# Arduino_sheet.net
KiCad netlist of a schematic drawn in Altium Designer
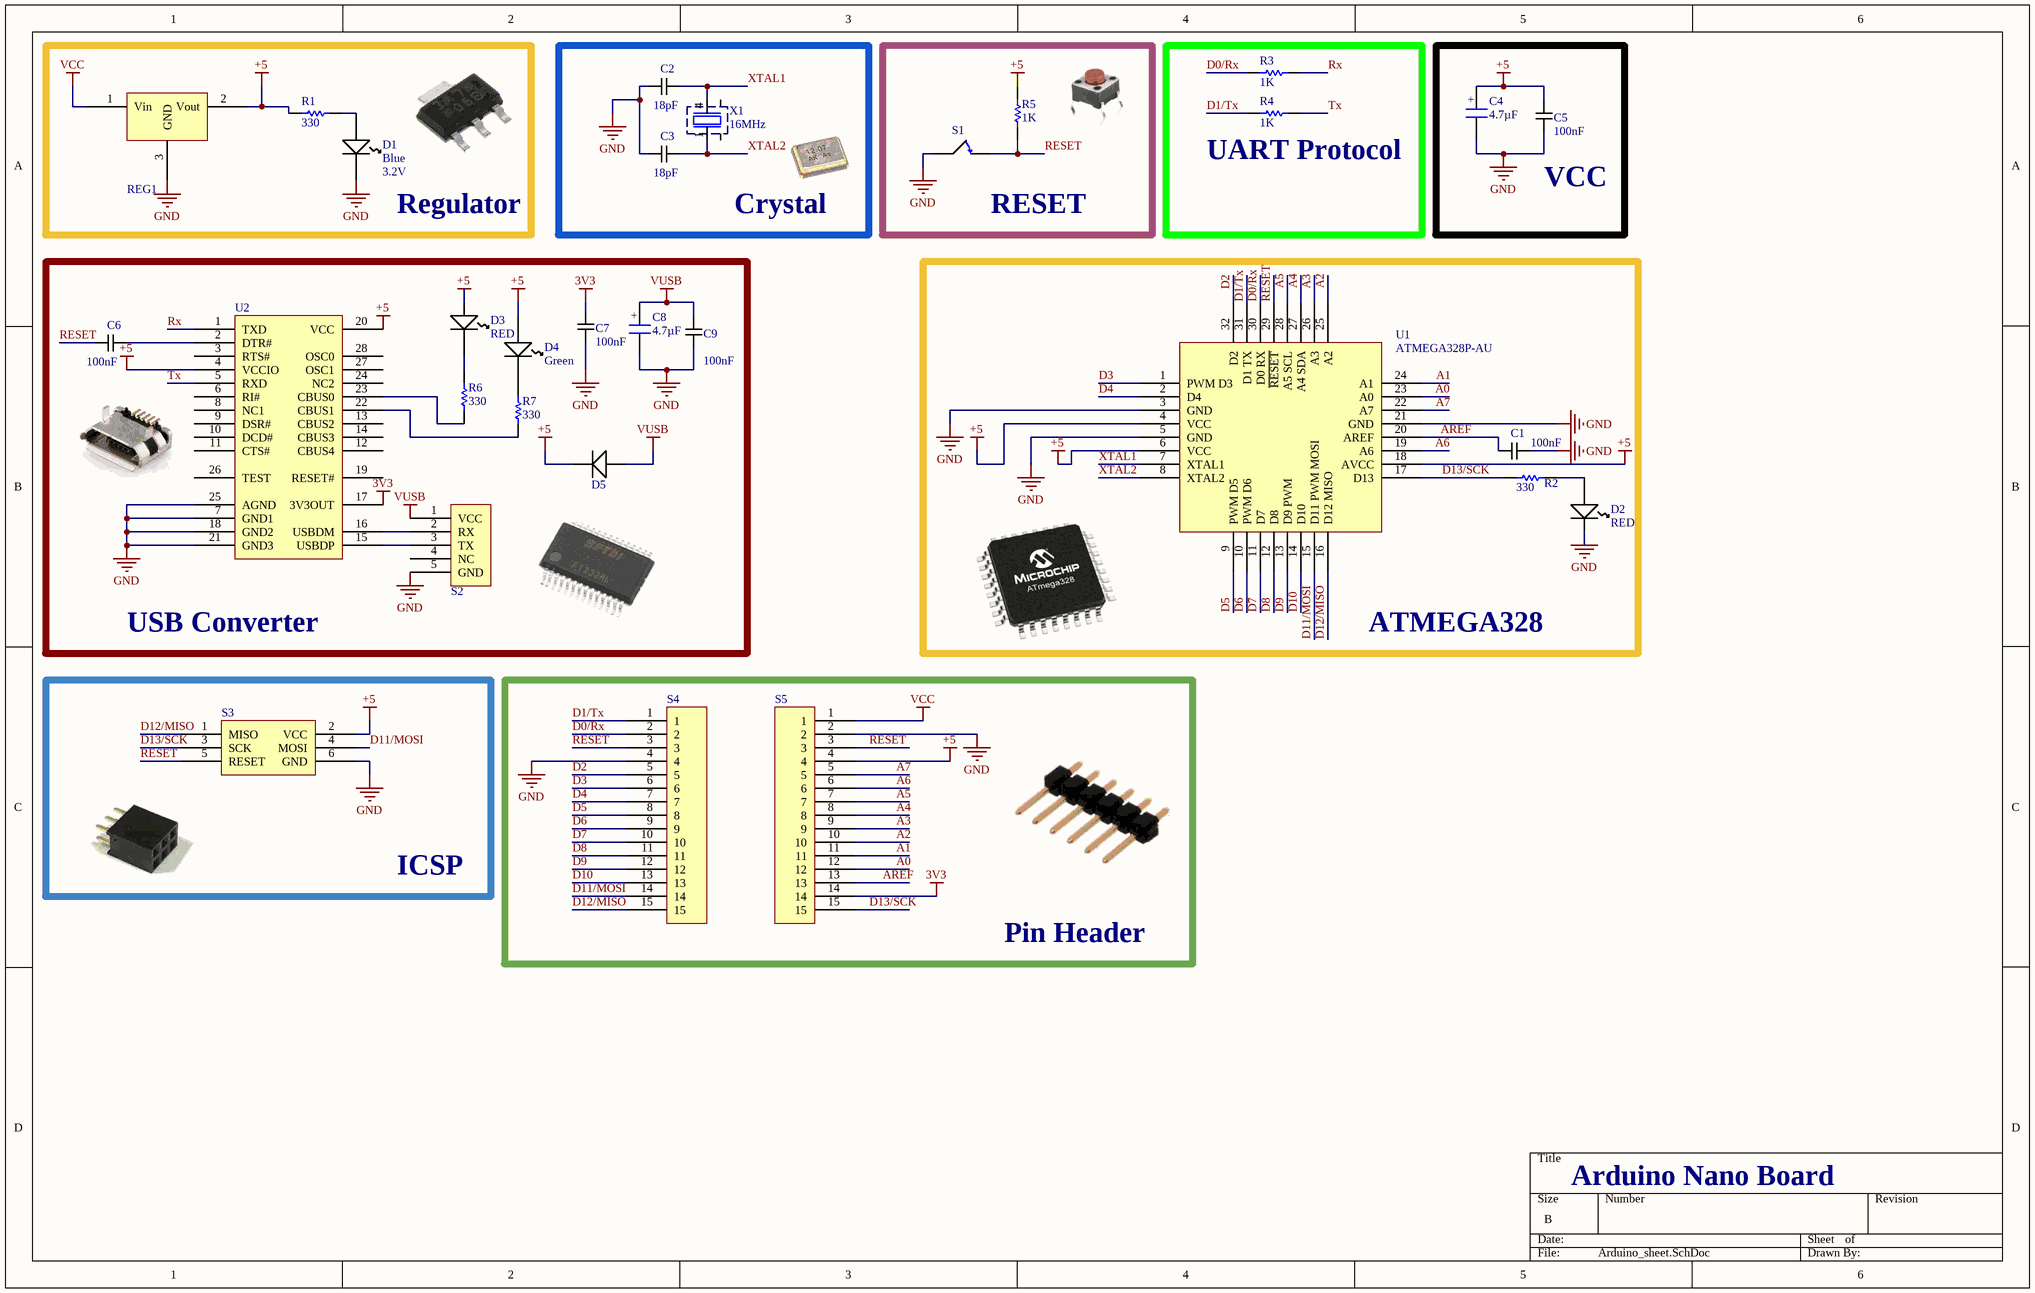
[diagram p0: Arduino_sheet.SchDoc]

(export (version "E")
  (design (tool "Eeschema 10.0.6"))
  (components
    (comp (ref "C1")
      (value "100nF Ceramic Multilayer Capacitor_1")
      (footprint "CAPCP2012X09N")
      (description "AVX 0805 Standard 100nF Ceramic Multilayer Capacitor, 50 V dc X7R Dielectric ±10% SMD")
      (fields
        (field (name "MANUFACTURER") "AVX")
        (field (name "VOLTAGE") "50V")
        (field (name "CAPACITANCE") "100nF")
        (field (name "CREATOR") "Ritesh Kanjee")
      )
      (libsource (lib "RS Components - Capacitors") (part "100nF Ceramic Multilayer Capacitor_1"))
    )
    (comp (ref "C2")
      (value "C0805C180J5GACTU")
      (footprint "CAPCP2012X09N")
      (description "18pF Ceramic Multilayer Capacitor, 50 V dc C0G Dielectric ±5% SMD")
      (fields
        (field (name "MANUFACTURER") "Kemet")
        (field (name "VOLTAGE") "50V")
        (field (name "CAPACITANCE") "18pF")
        (field (name "CREATOR") "Ritesh Kanjee")
      )
      (libsource (lib "RS Components - Capacitors") (part "18pF Ceramic Multilayer Capacitor, 50 V dc C0G Dielectric ±5% SMD"))
    )
    (comp (ref "C3")
      (value "C0805C180J5GACTU")
      (footprint "CAPCP2012X09N")
      (description "18pF Ceramic Multilayer Capacitor, 50 V dc C0G Dielectric ±5% SMD")
      (fields
        (field (name "MANUFACTURER") "Kemet")
        (field (name "VOLTAGE") "50V")
        (field (name "CAPACITANCE") "18pF")
        (field (name "CREATOR") "Ritesh Kanjee")
      )
      (libsource (lib "RS Components - Capacitors") (part "18pF Ceramic Multilayer Capacitor, 50 V dc C0G Dielectric ±5% SMD"))
    )
    (comp (ref "C4")
      (value "4.7µF")
      (footprint "CASE A - 3216X18")
      (description "Capacitor,tantalum,SMT,16V,4.7uF,10%,A-case")
      (fields
        (field (name "TOLERANCE") "10%")
        (field (name "VOLTAGE") "16V")
        (field (name "PUBLISHER") "DPSS")
      )
      (libsource (lib "RS Components - Capacitors") (part "4.7µF Tant RS 496-3545"))
    )
    (comp (ref "C5")
      (value "100nF Ceramic Multilayer Capacitor_1")
      (footprint "CAPCP2012X09N")
      (description "AVX 0805 Standard 100nF Ceramic Multilayer Capacitor, 50 V dc X7R Dielectric ±10% SMD")
      (fields
        (field (name "MANUFACTURER") "AVX")
        (field (name "VOLTAGE") "50V")
        (field (name "CAPACITANCE") "100nF")
        (field (name "CREATOR") "Ritesh Kanjee")
      )
      (libsource (lib "RS Components - Capacitors") (part "100nF Ceramic Multilayer Capacitor_1"))
    )
    (comp (ref "C6")
      (value "100nF Ceramic Multilayer Capacitor_1")
      (footprint "CAPCP2012X09N")
      (description "AVX 0805 Standard 100nF Ceramic Multilayer Capacitor, 50 V dc X7R Dielectric ±10% SMD")
      (fields
        (field (name "MANUFACTURER") "AVX")
        (field (name "VOLTAGE") "50V")
        (field (name "CAPACITANCE") "100nF")
        (field (name "CREATOR") "Ritesh Kanjee")
      )
      (libsource (lib "RS Components - Capacitors") (part "100nF Ceramic Multilayer Capacitor_1"))
    )
    (comp (ref "C7")
      (value "100nF Ceramic Multilayer Capacitor_1")
      (footprint "CAPCP2012X09N")
      (description "AVX 0805 Standard 100nF Ceramic Multilayer Capacitor, 50 V dc X7R Dielectric ±10% SMD")
      (fields
        (field (name "MANUFACTURER") "AVX")
        (field (name "VOLTAGE") "50V")
        (field (name "CAPACITANCE") "100nF")
        (field (name "CREATOR") "Ritesh Kanjee")
      )
      (libsource (lib "RS Components - Capacitors") (part "100nF Ceramic Multilayer Capacitor_1"))
    )
    (comp (ref "C8")
      (value "4.7µF")
      (footprint "CASE A - 3216X18")
      (description "Capacitor,tantalum,SMT,16V,4.7uF,10%,A-case")
      (fields
        (field (name "TOLERANCE") "10%")
        (field (name "VOLTAGE") "16V")
        (field (name "PUBLISHER") "DPSS")
      )
      (libsource (lib "RS Components - Capacitors") (part "4.7µF Tant RS 496-3545"))
    )
    (comp (ref "C9")
      (value "100nF Ceramic Multilayer Capacitor_1")
      (footprint "CAPCP2012X09N")
      (description "AVX 0805 Standard 100nF Ceramic Multilayer Capacitor, 50 V dc X7R Dielectric ±10% SMD")
      (fields
        (field (name "MANUFACTURER") "AVX")
        (field (name "VOLTAGE") "50V")
        (field (name "CAPACITANCE") "100nF")
        (field (name "CREATOR") "Ritesh Kanjee")
      )
      (libsource (lib "RS Components - Capacitors") (part "100nF Ceramic Multilayer Capacitor_1"))
    )
    (comp (ref "D1")
      (value "Kingbright Blue LED, 60 mcd 120 ° 0805")
      (footprint "LED1913X12NBLUE")
      (fields
        (field (name "MANUFACTURER") "KingBright")
        (field (name "MANUFACTURER PART NO.") "KP-2012PBC-A")
        (field (name "COLOR") "Blue")
        (field (name "FORWARD VOLTAGE") "3.2V")
        (field (name "CREATOR") "Ritesh Kanjee")
      )
      (libsource (lib "KingBright LEDs") (part "Kingbright Blue LED, 60 mcd 120 ° 0805"))
    )
    (comp (ref "D2")
      (value "Kingbright Red LED, 100 mcd 120 ° 0805")
      (footprint "LED1913X12NRED")
      (fields
        (field (name "MANUFACTURER") "KingBright")
        (field (name "MANUFACTURER PART NO.") "KP-2012SRC-PRV")
        (field (name "COLOR") "RED")
        (field (name "CREATOR") "Ritesh Kanjee")
      )
      (libsource (lib "KingBright LEDs") (part "Kingbright Red LED, 100 mcd 120 ° 0805"))
    )
    (comp (ref "D3")
      (value "Kingbright Red LED, 100 mcd 120 ° 0805")
      (footprint "LED1913X12NRED")
      (fields
        (field (name "MANUFACTURER") "KingBright")
        (field (name "MANUFACTURER PART NO.") "KP-2012SRC-PRV")
        (field (name "COLOR") "RED")
        (field (name "CREATOR") "Ritesh Kanjee")
      )
      (libsource (lib "KingBright LEDs") (part "Kingbright Red LED, 100 mcd 120 ° 0805"))
    )
    (comp (ref "D4")
      (value "Kingbright Green LED, 70 mcd 120 ° 0805")
      (footprint "LED1913X12NGREEN")
      (fields
        (field (name "MANUFACTURER") "KingBright")
        (field (name "MANUFACTURER PART NO.") "KP-2012MGC")
        (field (name "COLOR") "Green")
        (field (name "CREATOR") "Ritesh Kanjee")
      )
      (libsource (lib "KingBright LEDs") (part "Kingbright Green LED, 70 mcd 120 ° 0805"))
    )
    (comp (ref "D5")
      (value "Panasonic DB2J20900L Schottky Diode, 0.5A, 20V, 2.4ns, 2-Pin SMini2 F5 B")
      (footprint "DIOM1712X07N")
      (fields
        (field (name "MANUFACTURER") "Panasonic")
        (field (name "MANUFACTURER PART NO.") "DB2J20900L")
        (field (name "CREATED BY") "R Kanjee")
      )
      (libsource (lib "Panasonic Diodes") (part "Schottky Diode, 0.5A, 20V, 2.4ns, 2-Pin SMini2 F5 B"))
    )
    (comp (ref "R1")
      (value "330")
      (description "Resistor")
      (libsource (lib "Simulation Generic Components") (part "Resistor"))
    )
    (comp (ref "R2")
      (value "330")
      (description "Resistor")
      (libsource (lib "Simulation Generic Components") (part "Resistor"))
    )
    (comp (ref "R3")
      (value "1K")
      (description "Resistor")
      (libsource (lib "Simulation Generic Components") (part "Resistor"))
    )
    (comp (ref "R4")
      (value "1K")
      (description "Resistor")
      (libsource (lib "Simulation Generic Components") (part "Resistor"))
    )
    (comp (ref "R5")
      (value "1K")
      (description "Resistor")
      (libsource (lib "Simulation Generic Components") (part "Resistor"))
    )
    (comp (ref "R6")
      (value "330")
      (description "Resistor")
      (libsource (lib "Simulation Generic Components") (part "Resistor"))
    )
    (comp (ref "R7")
      (value "330")
      (description "Resistor")
      (libsource (lib "Simulation Generic Components") (part "Resistor"))
    )
    (comp (ref "REG1")
      (value "LM1117MP-5.0/NOPB, Low Dropout Voltage Regulator, 1.5A, 5 V ±1%, 4-Pin SOT-223")
      (footprint "SOT230P700X180-4N")
      (fields (field (name "MANUFACTURER") "Texas Instruments") (field (name "CREATED BY") "R Kanjee"))
      (libsource (lib "TI Low Dropout Voltage Regulator") (part "LM1117MP-5.0"))
    )
    (comp (ref "S1")
      (value "Tactile Switch SPST- NO 0.05A @24V")
      (footprint "Tactile Switch")
      (fields
        (field (name "MANUFACTURER") "Omron")
        (field (name "MANUFACTURER PART NO.") "B3F1000")
        (field (name "CREATOR") "R Kanjee")
      )
      (libsource (lib "Omron Tactile Switches") (part "Tactile Switch SPST- NO 0.05A @24V"))
    )
    (comp (ref "S2")
      (value "NewMolex Right Angle SMT Female Type B Micro USB Connector, 30 V ac, 1.8A")
      (footprint "MicroUSB")
      (fields
        (field (name "MANUFACTURER") "Molex")
        (field (name "MANUFACTURER PART NO.") "105017-0001")
        (field (name "CREATOR") "R Kanjee")
      )
      (libsource (lib "Molex Connectors") (part "Micro USB Connector, 30 V ac, 1.8A"))
    )
    (comp (ref "S3")
      (value "Programming Headers Dual Row")
      (footprint "ISP HEADER")
      (fields
        (field (name "MANUFACTURER") "FCI")
        (field (name "MANUFACTURER PART NO.") "68000-236HLF")
        (field (name "CREATED BY") "R Kanjee")
      )
      (libsource (lib "PCB Headers") (part "Programming ISP, Programming Headers Dual Row"))
    )
    (comp (ref "S4")
      (value "connector;str header;single row;.1 cont centers;.095 tail;gold or gtx;36 contact")
      (footprint "Header")
      (fields
        (field (name "MANUFACTURER") "FCI")
        (field (name "MANUFACTURER PART NO.") "68000-236HLF")
        (field (name "CREATED BY") "R Kanjee")
      )
      (libsource (lib "") (part "Single row; PCB headers_1"))
    )
    (comp (ref "S5")
      (value "connector;str header;single row;.1 cont centers;.095 tail;gold or gtx;36 contact")
      (footprint "Header")
      (fields
        (field (name "MANUFACTURER") "FCI")
        (field (name "MANUFACTURER PART NO.") "68000-236HLF")
        (field (name "CREATED BY") "R Kanjee")
      )
      (libsource (lib "PCB Headers") (part "Single row; PCB headers"))
    )
    (comp (ref "U1")
      (value "ATMEGA328P-AU")
      (footprint "TQFP80P900X900X120-32N")
      (description "ATMEGA328P-AU, 8 bit AVR Microcontroller 20MHz 1 kB, 32 kB Flash, 2 kB RAM, I2C 32-Pin TQFP")
      (fields (field (name "CREATED BY") "Ritesh Kanjee"))
      (libsource (lib "Atmel Microcontrollers") (part "ATMEGA328P-AU"))
    )
    (comp (ref "U2")
      (value "FT232RL, Universal Asynchronous Receiver & Transmitter 3MBd, 28-Pin, SSOP")
      (footprint "SOP65P780X200-28N")
      (fields
        (field (name "MANUFACTURER PART NO.") "FT232RL")
        (field (name "MANUFACTURER") "FTDI Chip")
        (field (name "CREATOR") "R Kanjee")
      )
      (libsource (lib "FTDI RS232toUSB") (part "FT232RL USB to UART, Universal Asynchronous Receiver & Transmitter 3MBd, 28-Pin, SSOP"))
    )
    (comp (ref "X1")
      (value "16MHz")
      (footprint "Aker S5C Crystal")
      (description "Aker S5C SMT Crystal")
      (fields
        (field (name "MANUFACTURER") "Aker")
        (field (name "MANUFACTURER PART #") "C5S-16.000-12-3030-X")
        (field (name "CREATOR") "R Kanjee")
      )
      (libsource (lib "Aker Crystals") (part "Aker  C5S-16.000-12-3030-X"))
    )
  )
  (nets
    (net (code "1") (name "+5") (class "Default")
      (node (ref "C4") (pin "1") (pinfunction "1_1") (pintype "passive"))
      (node (ref "C5") (pin "2") (pinfunction "2_2") (pintype "passive"))
      (node (ref "D3") (pin "1") (pinfunction "A_1") (pintype "passive"))
      (node (ref "D4") (pin "1") (pinfunction "A_1") (pintype "passive"))
      (node (ref "D5") (pin "1") (pinfunction "1_1") (pintype "passive"))
      (node (ref "R1") (pin "1") (pinfunction "1_1") (pintype "passive"))
      (node (ref "R5") (pin "2") (pinfunction "2_2") (pintype "passive"))
      (node (ref "REG1") (pin "2") (pinfunction "Vout_2") (pintype "passive"))
      (node (ref "S3") (pin "2") (pinfunction "VCC_2") (pintype "passive"))
      (node (ref "S5") (pin "4") (pinfunction "4_4") (pintype "passive"))
      (node (ref "U1") (pin "18") (pinfunction "AVCC_18") (pintype "passive"))
      (node (ref "U1") (pin "4") (pinfunction "VCC_4") (pintype "passive"))
      (node (ref "U1") (pin "6") (pinfunction "VCC_6") (pintype "passive"))
      (node (ref "U2") (pin "20") (pinfunction "VCC_20") (pintype "passive"))
      (node (ref "U2") (pin "4") (pinfunction "VCCIO_4") (pintype "passive"))
    )
    (net (code "2") (name "/A0") (class "Default")
      (node (ref "S5") (pin "12") (pinfunction "12_12") (pintype "passive"))
      (node (ref "U1") (pin "23") (pinfunction "A0_23") (pintype "passive"))
    )
    (net (code "3") (name "/A1") (class "Default")
      (node (ref "S5") (pin "11") (pinfunction "11_11") (pintype "passive"))
      (node (ref "U1") (pin "24") (pinfunction "A1_24") (pintype "passive"))
    )
    (net (code "4") (name "/A2") (class "Default")
      (node (ref "S5") (pin "10") (pinfunction "10_10") (pintype "passive"))
      (node (ref "U1") (pin "25") (pinfunction "A2_25") (pintype "passive"))
    )
    (net (code "5") (name "/A3") (class "Default")
      (node (ref "S5") (pin "9") (pinfunction "9_9") (pintype "passive"))
      (node (ref "U1") (pin "26") (pinfunction "A3_26") (pintype "passive"))
    )
    (net (code "6") (name "/A4") (class "Default")
      (node (ref "S5") (pin "8") (pinfunction "8_8") (pintype "passive"))
      (node (ref "U1") (pin "27") (pinfunction "A4_SDA_27") (pintype "passive"))
    )
    (net (code "7") (name "/A5") (class "Default")
      (node (ref "S5") (pin "7") (pinfunction "7_7") (pintype "passive"))
      (node (ref "U1") (pin "28") (pinfunction "A5_SCL_28") (pintype "passive"))
    )
    (net (code "8") (name "/A6") (class "Default")
      (node (ref "S5") (pin "6") (pinfunction "6_6") (pintype "passive"))
      (node (ref "U1") (pin "19") (pinfunction "A6_19") (pintype "passive"))
    )
    (net (code "9") (name "/A7") (class "Default")
      (node (ref "S5") (pin "5") (pinfunction "5_5") (pintype "passive"))
      (node (ref "U1") (pin "22") (pinfunction "A7_22") (pintype "passive"))
    )
    (net (code "10") (name "/AREF") (class "Default")
      (node (ref "C1") (pin "1") (pinfunction "1_1") (pintype "passive"))
      (node (ref "S5") (pin "13") (pinfunction "13_13") (pintype "passive"))
      (node (ref "U1") (pin "20") (pinfunction "AREF_20") (pintype "passive"))
    )
    (net (code "11") (name "/D0{slash}Rx") (class "Default")
      (node (ref "R3") (pin "1") (pinfunction "1_1") (pintype "passive"))
      (node (ref "S4") (pin "2") (pinfunction "2_2") (pintype "passive"))
      (node (ref "U1") (pin "30") (pinfunction "D0_RX_30") (pintype "passive"))
    )
    (net (code "12") (name "/D1{slash}Tx") (class "Default")
      (node (ref "R4") (pin "1") (pinfunction "1_1") (pintype "passive"))
      (node (ref "S4") (pin "1") (pinfunction "1_1") (pintype "passive"))
      (node (ref "U1") (pin "31") (pinfunction "D1_TX_31") (pintype "passive"))
    )
    (net (code "13") (name "/D2") (class "Default")
      (node (ref "S4") (pin "5") (pinfunction "5_5") (pintype "passive"))
      (node (ref "U1") (pin "32") (pinfunction "D2_32") (pintype "passive"))
    )
    (net (code "14") (name "/D3") (class "Default")
      (node (ref "S4") (pin "6") (pinfunction "6_6") (pintype "passive"))
      (node (ref "U1") (pin "1") (pinfunction "PWM_D3_1") (pintype "passive"))
    )
    (net (code "15") (name "/D4") (class "Default")
      (node (ref "S4") (pin "7") (pinfunction "7_7") (pintype "passive"))
      (node (ref "U1") (pin "2") (pinfunction "D4_2") (pintype "passive"))
    )
    (net (code "16") (name "/D5") (class "Default")
      (node (ref "S4") (pin "8") (pinfunction "8_8") (pintype "passive"))
      (node (ref "U1") (pin "9") (pinfunction "PWM_D5_9") (pintype "passive"))
    )
    (net (code "17") (name "/D6") (class "Default")
      (node (ref "S4") (pin "9") (pinfunction "9_9") (pintype "passive"))
      (node (ref "U1") (pin "10") (pinfunction "PWM_D6_10") (pintype "passive"))
    )
    (net (code "18") (name "/D7") (class "Default")
      (node (ref "S4") (pin "10") (pinfunction "10_10") (pintype "passive"))
      (node (ref "U1") (pin "11") (pinfunction "D7_11") (pintype "passive"))
    )
    (net (code "19") (name "/D8") (class "Default")
      (node (ref "S4") (pin "11") (pinfunction "11_11") (pintype "passive"))
      (node (ref "U1") (pin "12") (pinfunction "D8_12") (pintype "passive"))
    )
    (net (code "20") (name "/D9") (class "Default")
      (node (ref "S4") (pin "12") (pinfunction "12_12") (pintype "passive"))
      (node (ref "U1") (pin "13") (pinfunction "D9_PWM_13") (pintype "passive"))
    )
    (net (code "21") (name "/D10") (class "Default")
      (node (ref "S4") (pin "13") (pinfunction "13_13") (pintype "passive"))
      (node (ref "U1") (pin "14") (pinfunction "D10_14") (pintype "passive"))
    )
    (net (code "22") (name "/D11{slash}MOSI") (class "Default")
      (node (ref "S3") (pin "4") (pinfunction "MOSI_4") (pintype "passive"))
      (node (ref "S4") (pin "14") (pinfunction "14_14") (pintype "passive"))
      (node (ref "U1") (pin "15") (pinfunction "D11_PWM_MOSI_15") (pintype "passive"))
    )
    (net (code "23") (name "/D12{slash}MISO") (class "Default")
      (node (ref "S3") (pin "1") (pinfunction "MISO_1") (pintype "passive"))
      (node (ref "S4") (pin "15") (pinfunction "15_15") (pintype "passive"))
      (node (ref "U1") (pin "16") (pinfunction "D12_MISO_16") (pintype "passive"))
    )
    (net (code "24") (name "/D13{slash}SCK") (class "Default")
      (node (ref "R2") (pin "1") (pinfunction "1_1") (pintype "passive"))
      (node (ref "S3") (pin "3") (pinfunction "SCK_3") (pintype "passive"))
      (node (ref "S5") (pin "15") (pinfunction "15_15") (pintype "passive"))
      (node (ref "U1") (pin "17") (pinfunction "D13_17") (pintype "passive"))
    )
    (net (code "25") (name "/RESET") (class "Default")
      (node (ref "C6") (pin "1") (pinfunction "1_1") (pintype "passive"))
      (node (ref "R5") (pin "1") (pinfunction "1_1") (pintype "passive"))
      (node (ref "S1") (pin "1") (pinfunction "1_1") (pintype "passive"))
      (node (ref "S3") (pin "5") (pinfunction "RESET_5") (pintype "passive"))
      (node (ref "S4") (pin "3") (pinfunction "3_3") (pintype "passive"))
      (node (ref "S5") (pin "3") (pinfunction "3_3") (pintype "passive"))
      (node (ref "U1") (pin "29") (pinfunction "~{RESET}_29") (pintype "passive"))
    )
    (net (code "26") (name "/Rx") (class "Default")
      (node (ref "R3") (pin "2") (pinfunction "2_2") (pintype "passive"))
      (node (ref "U2") (pin "1") (pinfunction "TXD_1") (pintype "passive"))
    )
    (net (code "27") (name "/Tx") (class "Default")
      (node (ref "R4") (pin "2") (pinfunction "2_2") (pintype "passive"))
      (node (ref "U2") (pin "5") (pinfunction "RXD_5") (pintype "passive"))
    )
    (net (code "28") (name "/XTAL1") (class "Default")
      (node (ref "C2") (pin "2") (pinfunction "2_2") (pintype "passive"))
      (node (ref "U1") (pin "7") (pinfunction "XTAL1_7") (pintype "passive"))
      (node (ref "X1") (pin "4") (pinfunction "4_4") (pintype "passive"))
    )
    (net (code "29") (name "/XTAL2") (class "Default")
      (node (ref "C3") (pin "2") (pinfunction "2_2") (pintype "passive"))
      (node (ref "U1") (pin "8") (pinfunction "XTAL2_8") (pintype "passive"))
      (node (ref "X1") (pin "1") (pinfunction "1_1") (pintype "passive"))
    )
    (net (code "30") (name "3V3") (class "Default")
      (node (ref "C7") (pin "1") (pinfunction "1_1") (pintype "passive"))
      (node (ref "S5") (pin "14") (pinfunction "14_14") (pintype "passive"))
      (node (ref "U2") (pin "17") (pinfunction "3V3OUT_17") (pintype "passive"))
    )
    (net (code "31") (name "GND") (class "Default")
      (node (ref "C1") (pin "2") (pinfunction "2_2") (pintype "passive"))
      (node (ref "C2") (pin "1") (pinfunction "1_1") (pintype "passive"))
      (node (ref "C3") (pin "1") (pinfunction "1_1") (pintype "passive"))
      (node (ref "C4") (pin "2") (pinfunction "2_2") (pintype "passive"))
      (node (ref "C5") (pin "1") (pinfunction "1_1") (pintype "passive"))
      (node (ref "C7") (pin "2") (pinfunction "2_2") (pintype "passive"))
      (node (ref "C8") (pin "2") (pinfunction "2_2") (pintype "passive"))
      (node (ref "C9") (pin "1") (pinfunction "1_1") (pintype "passive"))
      (node (ref "D1") (pin "2") (pinfunction "K_2") (pintype "passive"))
      (node (ref "D2") (pin "2") (pinfunction "K_2") (pintype "passive"))
      (node (ref "REG1") (pin "3") (pinfunction "GND_3") (pintype "passive"))
      (node (ref "S1") (pin "1") (pinfunction "1_1") (pintype "passive"))
      (node (ref "S2") (pin "5") (pinfunction "GND_5") (pintype "passive"))
      (node (ref "S3") (pin "6") (pinfunction "GND_6") (pintype "passive"))
      (node (ref "S4") (pin "4") (pinfunction "4_4") (pintype "passive"))
      (node (ref "S5") (pin "2") (pinfunction "2_2") (pintype "passive"))
      (node (ref "U1") (pin "21") (pinfunction "GND_21") (pintype "passive"))
      (node (ref "U1") (pin "3") (pinfunction "GND_3") (pintype "passive"))
      (node (ref "U1") (pin "5") (pinfunction "GND_5") (pintype "passive"))
      (node (ref "U2") (pin "18") (pinfunction "GND2_18") (pintype "passive"))
      (node (ref "U2") (pin "21") (pinfunction "GND3_21") (pintype "passive"))
      (node (ref "U2") (pin "25") (pinfunction "AGND_25") (pintype "passive"))
      (node (ref "U2") (pin "7") (pinfunction "GND1_7") (pintype "passive"))
    )
    (net (code "32") (name "Net-(D1-A)") (class "Default")
      (node (ref "D1") (pin "1") (pinfunction "A_1") (pintype "passive"))
      (node (ref "R1") (pin "2") (pinfunction "2_2") (pintype "passive"))
    )
    (net (code "33") (name "Net-(D2-A)") (class "Default")
      (node (ref "D2") (pin "1") (pinfunction "A_1") (pintype "passive"))
      (node (ref "R2") (pin "2") (pinfunction "2_2") (pintype "passive"))
    )
    (net (code "34") (name "Net-(D3-K)") (class "Default")
      (node (ref "D3") (pin "2") (pinfunction "K_2") (pintype "passive"))
      (node (ref "R6") (pin "2") (pinfunction "2_2") (pintype "passive"))
    )
    (net (code "35") (name "Net-(D4-K)") (class "Default")
      (node (ref "D4") (pin "2") (pinfunction "K_2") (pintype "passive"))
      (node (ref "R7") (pin "2") (pinfunction "2_2") (pintype "passive"))
    )
    (net (code "36") (name "Net-(S2-RX)") (class "Default")
      (node (ref "S2") (pin "2") (pinfunction "RX_2") (pintype "passive"))
      (node (ref "U2") (pin "16") (pinfunction "USBDM_16") (pintype "passive"))
    )
    (net (code "37") (name "Net-(S2-TX)") (class "Default")
      (node (ref "S2") (pin "3") (pinfunction "TX_3") (pintype "passive"))
      (node (ref "U2") (pin "15") (pinfunction "USBDP_15") (pintype "passive"))
    )
    (net (code "38") (name "Net-(U2-CBUS0)") (class "Default")
      (node (ref "R6") (pin "1") (pinfunction "1_1") (pintype "passive"))
      (node (ref "U2") (pin "23") (pinfunction "CBUS0_23") (pintype "passive"))
    )
    (net (code "39") (name "Net-(U2-CBUS1)") (class "Default")
      (node (ref "R7") (pin "1") (pinfunction "1_1") (pintype "passive"))
      (node (ref "U2") (pin "22") (pinfunction "CBUS1_22") (pintype "passive"))
    )
    (net (code "40") (name "Net-(U2-DTR#)") (class "Default")
      (node (ref "C6") (pin "2") (pinfunction "2_2") (pintype "passive"))
      (node (ref "U2") (pin "2") (pinfunction "DTR#_2") (pintype "passive"))
    )
    (net (code "41") (name "VCC") (class "Default")
      (node (ref "REG1") (pin "1") (pinfunction "Vin_1") (pintype "passive"))
      (node (ref "S5") (pin "1") (pinfunction "1_1") (pintype "passive"))
    )
    (net (code "42") (name "VUSB") (class "Default")
      (node (ref "C8") (pin "1") (pinfunction "1_1") (pintype "passive"))
      (node (ref "C9") (pin "2") (pinfunction "2_2") (pintype "passive"))
      (node (ref "D5") (pin "2") (pinfunction "2_2") (pintype "passive"))
      (node (ref "S2") (pin "1") (pinfunction "VCC_1") (pintype "passive"))
    )
    (net (code "43") (name "unconnected-(S2-NC-Pad4)") (class "Default")
      (node (ref "S2") (pin "4") (pinfunction "NC_4") (pintype "passive"))
    )
    (net (code "44") (name "unconnected-(U2-CBUS2-Pad13)") (class "Default")
      (node (ref "U2") (pin "13") (pinfunction "CBUS2_13") (pintype "passive"))
    )
    (net (code "45") (name "unconnected-(U2-CBUS3-Pad14)") (class "Default")
      (node (ref "U2") (pin "14") (pinfunction "CBUS3_14") (pintype "passive"))
    )
    (net (code "46") (name "unconnected-(U2-CBUS4-Pad12)") (class "Default")
      (node (ref "U2") (pin "12") (pinfunction "CBUS4_12") (pintype "passive"))
    )
    (net (code "47") (name "unconnected-(U2-CTS#-Pad11)") (class "Default")
      (node (ref "U2") (pin "11") (pinfunction "CTS#_11") (pintype "passive"))
    )
    (net (code "48") (name "unconnected-(U2-DCD#-Pad10)") (class "Default")
      (node (ref "U2") (pin "10") (pinfunction "DCD#_10") (pintype "passive"))
    )
    (net (code "49") (name "unconnected-(U2-DSR#-Pad9)") (class "Default")
      (node (ref "U2") (pin "9") (pinfunction "DSR#_9") (pintype "passive"))
    )
    (net (code "50") (name "unconnected-(U2-NC1-Pad8)") (class "Default")
      (node (ref "U2") (pin "8") (pinfunction "NC1_8") (pintype "passive"))
    )
    (net (code "51") (name "unconnected-(U2-NC2-Pad24)") (class "Default")
      (node (ref "U2") (pin "24") (pinfunction "NC2_24") (pintype "passive"))
    )
    (net (code "52") (name "unconnected-(U2-OSC0-Pad28)") (class "Default")
      (node (ref "U2") (pin "28") (pinfunction "OSC0_28") (pintype "passive"))
    )
    (net (code "53") (name "unconnected-(U2-OSC1-Pad27)") (class "Default")
      (node (ref "U2") (pin "27") (pinfunction "OSC1_27") (pintype "passive"))
    )
    (net (code "54") (name "unconnected-(U2-RESET#-Pad19)") (class "Default")
      (node (ref "U2") (pin "19") (pinfunction "RESET#_19") (pintype "passive"))
    )
    (net (code "55") (name "unconnected-(U2-RI#-Pad6)") (class "Default")
      (node (ref "U2") (pin "6") (pinfunction "RI#_6") (pintype "passive"))
    )
    (net (code "56") (name "unconnected-(U2-RTS#-Pad3)") (class "Default")
      (node (ref "U2") (pin "3") (pinfunction "RTS#_3") (pintype "passive"))
    )
    (net (code "57") (name "unconnected-(U2-TEST-Pad26)") (class "Default")
      (node (ref "U2") (pin "26") (pinfunction "TEST_26") (pintype "passive"))
    )
    (net (code "58") (name "unconnected-(X1-Gnd-Pad2)") (class "Default")
      (node (ref "X1") (pin "2") (pinfunction "Gnd_2") (pintype "power_in"))
    )
    (net (code "59") (name "unconnected-(X1-Gnd-Pad3)") (class "Default")
      (node (ref "X1") (pin "3") (pinfunction "Gnd_3") (pintype "power_in"))
    )
  )
)
